# MMC-Badge.net
KiCad netlist of a schematic drawn in EAGLE
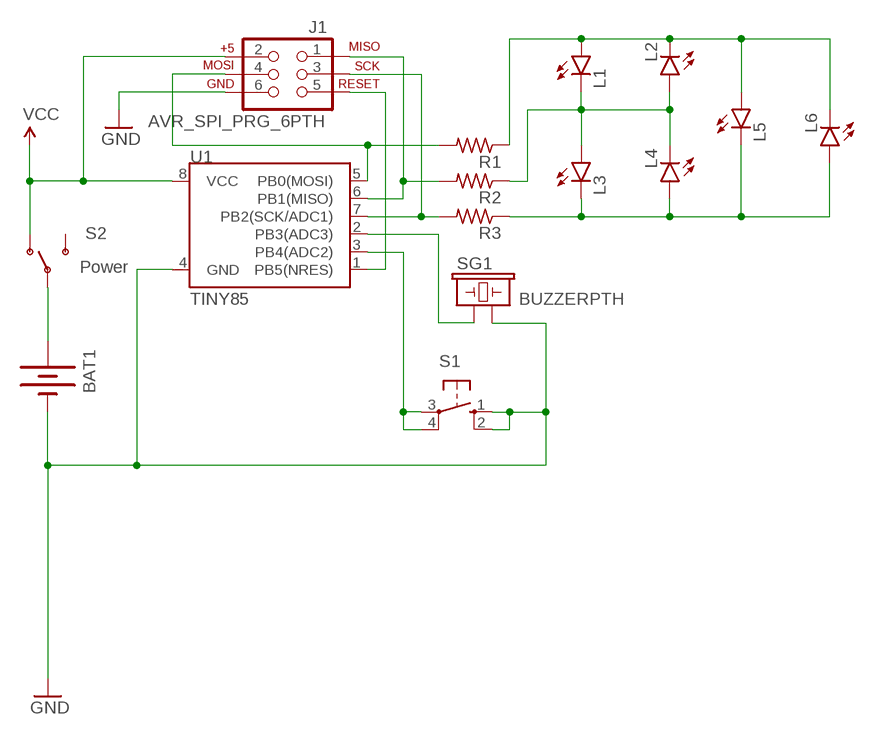
[diagram p0: schematic, sheet 1]

(export (version "E")
  (design (tool "Eeschema 10.0.6"))
  (components
    (comp (ref "BAT1")
      (value "BATTERY20PTH")
      (footprint "eagle-import:BATTCOM_20MM_PTH")
      (libsource (lib "eagle-import") (part "BATTERY20PTH"))
    )
    (comp (ref "J1")
      (value "AVR_SPI_PRG_6PTH")
      (footprint "eagle-import:2X3")
      (libsource (lib "eagle-import") (part "AVR_SPI_PRG_6PTH"))
    )
    (comp (ref "L1")
      (value "LED5MM")
      (footprint "eagle-import:LED5MM")
      (libsource (lib "eagle-import") (part "LED5MM"))
    )
    (comp (ref "L2")
      (value "LED5MM")
      (footprint "eagle-import:LED5MM")
      (libsource (lib "eagle-import") (part "LED5MM"))
    )
    (comp (ref "L3")
      (value "LED5MM")
      (footprint "eagle-import:LED5MM")
      (libsource (lib "eagle-import") (part "LED5MM"))
    )
    (comp (ref "L4")
      (value "LED5MM")
      (footprint "eagle-import:LED5MM")
      (libsource (lib "eagle-import") (part "LED5MM"))
    )
    (comp (ref "L5")
      (value "LED5MM")
      (footprint "eagle-import:LED5MM")
      (libsource (lib "eagle-import") (part "LED5MM"))
    )
    (comp (ref "L6")
      (value "LED5MM")
      (footprint "eagle-import:LED5MM")
      (libsource (lib "eagle-import") (part "LED5MM"))
    )
    (comp (ref "R1")
      (value "R-US_0204/7")
      (footprint "eagle-import:0204_7")
      (libsource (lib "eagle-import") (part "R-US_0204/7"))
    )
    (comp (ref "R2")
      (value "R-US_0204/7")
      (footprint "eagle-import:0204_7")
      (libsource (lib "eagle-import") (part "R-US_0204/7"))
    )
    (comp (ref "R3")
      (value "R-US_0204/7")
      (footprint "eagle-import:0204_7")
      (libsource (lib "eagle-import") (part "R-US_0204/7"))
    )
    (comp (ref "S1")
      (value "10-XX")
      (footprint "eagle-import:B3F-10XX")
      (fields (field (name "MPN") "B3F-1000"))
      (libsource (lib "eagle-import") (part "10-XX"))
    )
    (comp (ref "S2")
      (value "Power")
      (footprint "eagle-import:SWITCH-SPDT")
      (libsource (lib "eagle-import") (part "SWITCH-SPDTPTH"))
    )
    (comp (ref "SG1")
      (value "BUZZERPTH")
      (footprint "eagle-import:BUZZER-12MM")
      (libsource (lib "eagle-import") (part "BUZZERPTH"))
    )
    (comp (ref "U1")
      (value "TINY85")
      (footprint "eagle-import:DIP08")
      (libsource (lib "eagle-import") (part "ATTINY45TINY85-20-DIP"))
    )
  )
  (nets
    (net (code "1") (name "GND") (class "Default")
      (node (ref "BAT1") (pin "2") (pinfunction "-_2") (pintype "power_in"))
      (node (ref "J1") (pin "6") (pinfunction "6_6") (pintype "passive"))
      (node (ref "S1") (pin "1") (pinfunction "S_1") (pintype "passive"))
      (node (ref "S1") (pin "2") (pinfunction "S1_2") (pintype "passive"))
      (node (ref "SG1") (pin "-") (pinfunction "2_-") (pintype "passive"))
      (node (ref "U1") (pin "4") (pinfunction "GND_4") (pintype "bidirectional"))
    )
    (net (code "2") (name "Net-(BAT1-+)") (class "Default")
      (node (ref "BAT1") (pin "1") (pinfunction "+_1") (pintype "power_in"))
      (node (ref "S2") (pin "2") (pinfunction "P_2") (pintype "passive"))
    )
    (net (code "3") (name "Net-(L1-C)") (class "Default")
      (node (ref "L1") (pin "K") (pinfunction "C_K") (pintype "passive"))
      (node (ref "L2") (pin "A") (pinfunction "A_A") (pintype "passive"))
      (node (ref "L3") (pin "A") (pinfunction "A_A") (pintype "passive"))
      (node (ref "L4") (pin "K") (pinfunction "C_K") (pintype "passive"))
      (node (ref "R2") (pin "1") (pinfunction "1_1") (pintype "passive"))
    )
    (net (code "4") (name "Net-(L2-C)") (class "Default")
      (node (ref "L1") (pin "A") (pinfunction "A_A") (pintype "passive"))
      (node (ref "L2") (pin "K") (pinfunction "C_K") (pintype "passive"))
      (node (ref "L5") (pin "A") (pinfunction "A_A") (pintype "passive"))
      (node (ref "L6") (pin "K") (pinfunction "C_K") (pintype "passive"))
      (node (ref "R1") (pin "1") (pinfunction "1_1") (pintype "passive"))
    )
    (net (code "5") (name "Net-(L3-C)") (class "Default")
      (node (ref "L3") (pin "K") (pinfunction "C_K") (pintype "passive"))
      (node (ref "L4") (pin "A") (pinfunction "A_A") (pintype "passive"))
      (node (ref "L5") (pin "K") (pinfunction "C_K") (pintype "passive"))
      (node (ref "L6") (pin "A") (pinfunction "A_A") (pintype "passive"))
      (node (ref "R3") (pin "1") (pinfunction "1_1") (pintype "passive"))
    )
    (net (code "6") (name "Net-(S1-P)") (class "Default")
      (node (ref "S1") (pin "3") (pinfunction "P_3") (pintype "passive"))
      (node (ref "S1") (pin "4") (pinfunction "P1_4") (pintype "passive"))
      (node (ref "U1") (pin "3") (pinfunction "PB4(ADC2)_3") (pintype "bidirectional"))
    )
    (net (code "7") (name "Net-(SG1-1)") (class "Default")
      (node (ref "SG1") (pin "+") (pinfunction "1_+") (pintype "passive"))
      (node (ref "U1") (pin "2") (pinfunction "PB3(ADC3)_2") (pintype "bidirectional"))
    )
    (net (code "8") (name "Net-(U1-PB0(MOSI))") (class "Default")
      (node (ref "J1") (pin "4") (pinfunction "4_4") (pintype "passive"))
      (node (ref "R1") (pin "2") (pinfunction "2_2") (pintype "passive"))
      (node (ref "U1") (pin "5") (pinfunction "PB0(MOSI)_5") (pintype "bidirectional"))
    )
    (net (code "9") (name "Net-(U1-PB1(MISO))") (class "Default")
      (node (ref "J1") (pin "1") (pinfunction "1_1") (pintype "passive"))
      (node (ref "R2") (pin "2") (pinfunction "2_2") (pintype "passive"))
      (node (ref "U1") (pin "6") (pinfunction "PB1(MISO)_6") (pintype "bidirectional"))
    )
    (net (code "10") (name "Net-(U1-PB2(SCK{slash}ADC1))") (class "Default")
      (node (ref "J1") (pin "3") (pinfunction "3_3") (pintype "passive"))
      (node (ref "R3") (pin "2") (pinfunction "2_2") (pintype "passive"))
      (node (ref "U1") (pin "7") (pinfunction "PB2(SCK/ADC1)_7") (pintype "bidirectional"))
    )
    (net (code "11") (name "Net-(U1-PB5(NRES))") (class "Default")
      (node (ref "J1") (pin "5") (pinfunction "5_5") (pintype "passive"))
      (node (ref "U1") (pin "1") (pinfunction "PB5(NRES)_1") (pintype "bidirectional"))
    )
    (net (code "12") (name "VCC") (class "Default")
      (node (ref "J1") (pin "2") (pinfunction "2_2") (pintype "passive"))
      (node (ref "S2") (pin "1") (pinfunction "O_1") (pintype "passive"))
      (node (ref "U1") (pin "8") (pinfunction "VCC_8") (pintype "bidirectional"))
    )
    (net (code "13") (name "unconnected-(S2-S-Pad3)") (class "Default")
      (node (ref "S2") (pin "3") (pinfunction "S_3") (pintype "passive"))
    )
  )
)
